# Sheet1.net
KiCad netlist of a schematic drawn in Altium Designer
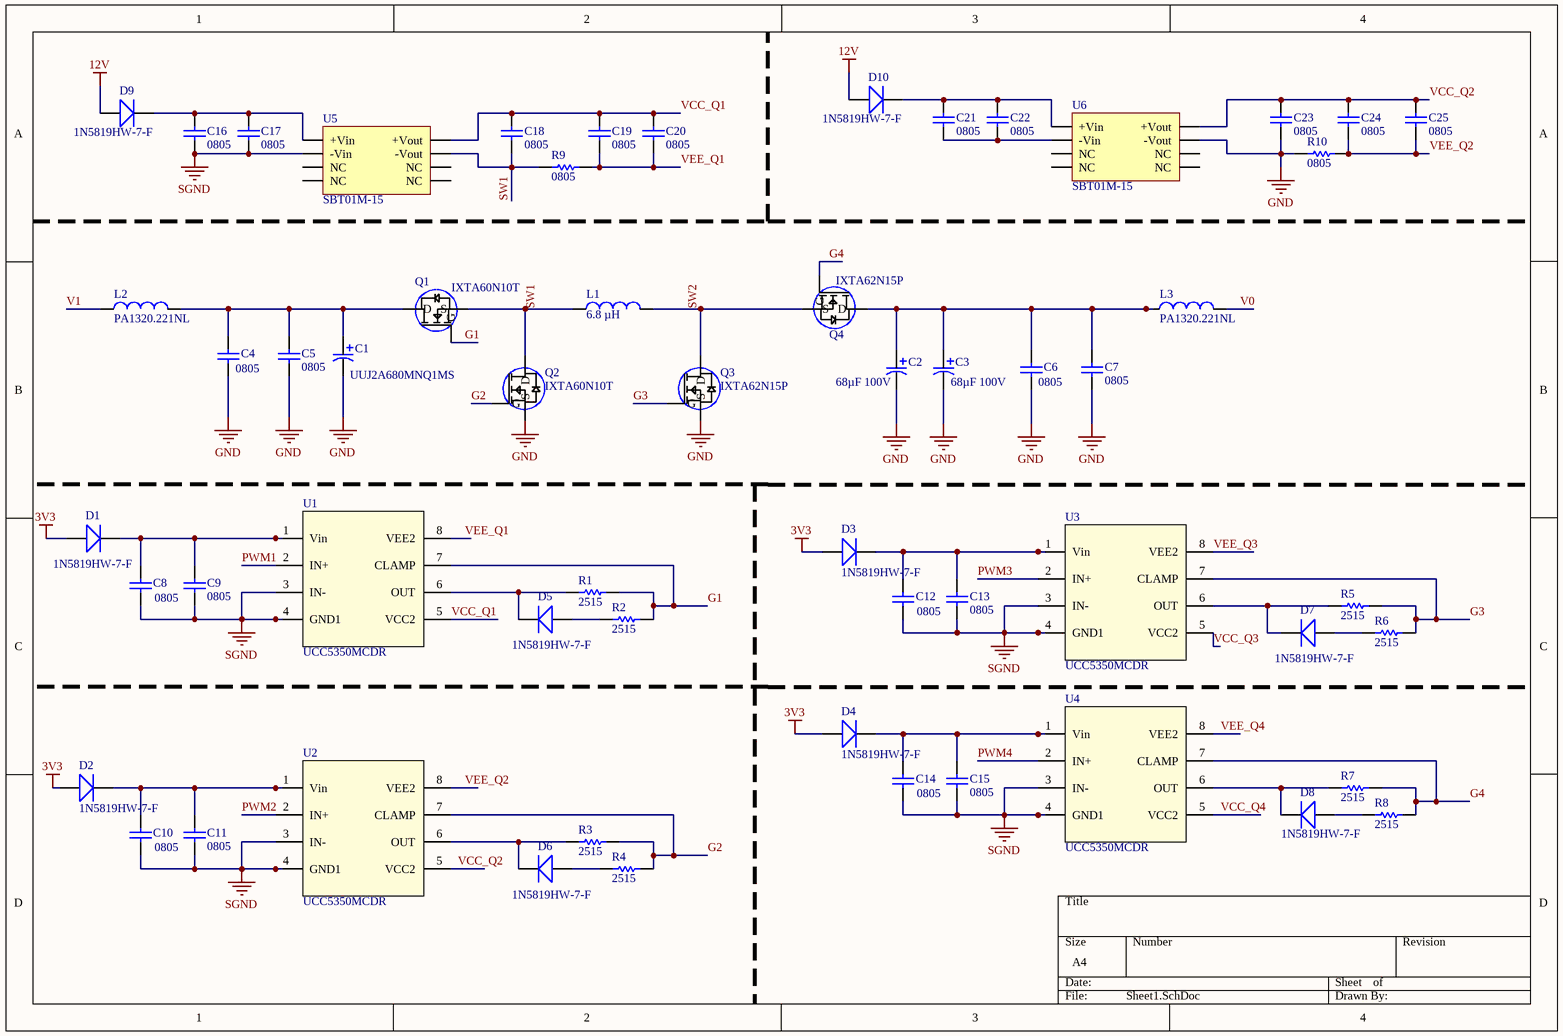
[diagram p0: Sheet1.SchDoc]

(export (version "E")
  (design (tool "Eeschema 10.0.6"))
  (components
    (comp (ref "C1")
      (value "UUJ2A680MNQ1MS")
      (footprint "UUJ2A680MNQ1MS")
      (description "68µF 100V Aluminum Electrolytic Capacitors")
      (libsource (lib "Schlib1") (part "UUJ2A680MNQ1MS"))
    )
    (comp (ref "C2")
      (value "68µF 100V")
      (footprint "UUJ2A680MNQ1MS")
      (description "68µF 100V Aluminum Electrolytic Capacitors")
      (libsource (lib "Schlib1") (part "UUJ2A680MNQ1MS"))
    )
    (comp (ref "C3")
      (value "68µF 100V")
      (footprint "UUJ2A680MNQ1MS")
      (description "68µF 100V Aluminum Electrolytic Capacitors")
      (libsource (lib "Schlib1") (part "UUJ2A680MNQ1MS"))
    )
    (comp (ref "C4")
      (value "0805")
      (footprint "0805 CAPACITOR")
      (description "1UF 100V CAP CER  X7S 0805")
      (libsource (lib "Schlib1") (part "0805CAP"))
    )
    (comp (ref "C5")
      (value "0805")
      (footprint "0805 CAPACITOR")
      (description "0.1UF 100V CAP CER X5R 0402")
      (libsource (lib "Schlib1") (part "0805CAP_1"))
    )
    (comp (ref "C6")
      (value "0805")
      (footprint "0805 CAPACITOR")
      (description "1UF 100V CAP CER  X7S 0805")
      (libsource (lib "Schlib1") (part "0805CAP"))
    )
    (comp (ref "C7")
      (value "0805")
      (footprint "0805 CAPACITOR")
      (description "0.1UF 100V CAP CER X5R 0402")
      (libsource (lib "Schlib1") (part "0805CAP_1"))
    )
    (comp (ref "C8")
      (value "0805")
      (footprint "0805 CAPACITOR")
      (description "4.7UF 100V CAP CER  X7S 0805")
      (libsource (lib "Schlib1") (part "0805 CAPACITANCE"))
    )
    (comp (ref "C9")
      (value "0805")
      (footprint "0805 CAPACITOR")
      (description "4.7UF 100V CAP CER  X7S 0805")
      (libsource (lib "Schlib1") (part "0805 CAPACITANCE"))
    )
    (comp (ref "C10")
      (value "0805")
      (footprint "0805 CAPACITOR")
      (description "4.7UF 100V CAP CER  X7S 0805")
      (libsource (lib "Schlib1") (part "0805 CAPACITANCE"))
    )
    (comp (ref "C11")
      (value "0805")
      (footprint "0805 CAPACITOR")
      (description "4.7UF 100V CAP CER  X7S 0805")
      (libsource (lib "Schlib1") (part "0805 CAPACITANCE"))
    )
    (comp (ref "C12")
      (value "0805")
      (footprint "0805 CAPACITOR")
      (description "4.7UF 100V CAP CER  X7S 0805")
      (libsource (lib "Schlib1") (part "0805 CAPACITANCE"))
    )
    (comp (ref "C13")
      (value "0805")
      (footprint "0805 CAPACITOR")
      (description "4.7UF 100V CAP CER  X7S 0805")
      (libsource (lib "Schlib1") (part "0805 CAPACITANCE"))
    )
    (comp (ref "C14")
      (value "0805")
      (footprint "0805 CAPACITOR")
      (description "4.7UF 100V CAP CER  X7S 0805")
      (libsource (lib "Schlib1") (part "0805 CAPACITANCE"))
    )
    (comp (ref "C15")
      (value "0805")
      (footprint "0805 CAPACITOR")
      (description "4.7UF 100V CAP CER  X7S 0805")
      (libsource (lib "Schlib1") (part "0805 CAPACITANCE"))
    )
    (comp (ref "C16")
      (value "0805")
      (footprint "0805 CAPACITOR")
      (description "4.7UF 100V CAP CER  X7S 0805")
      (libsource (lib "Schlib1") (part "0805 CAPACITANCE"))
    )
    (comp (ref "C17")
      (value "0805")
      (footprint "0805 CAPACITOR")
      (description "4.7UF 100V CAP CER  X7S 0805")
      (libsource (lib "Schlib1") (part "0805 CAPACITANCE"))
    )
    (comp (ref "C18")
      (value "0805")
      (footprint "0805 CAPACITOR")
      (description "4.7UF 100V CAP CER  X7S 0805")
      (libsource (lib "Schlib1") (part "0805 CAPACITANCE"))
    )
    (comp (ref "C19")
      (value "0805")
      (footprint "0805 CAPACITOR")
      (description "4.7UF 100V CAP CER  X7S 0805")
      (libsource (lib "Schlib1") (part "0805 CAPACITANCE"))
    )
    (comp (ref "C20")
      (value "0805")
      (footprint "0805 CAPACITOR")
      (description "4.7UF 100V CAP CER  X7S 0805")
      (libsource (lib "Schlib1") (part "0805 CAPACITANCE"))
    )
    (comp (ref "C21")
      (value "0805")
      (footprint "0805 CAPACITOR")
      (description "4.7UF 100V CAP CER  X7S 0805")
      (libsource (lib "Schlib1") (part "0805 CAPACITANCE"))
    )
    (comp (ref "C22")
      (value "0805")
      (footprint "0805 CAPACITOR")
      (description "4.7UF 100V CAP CER  X7S 0805")
      (libsource (lib "Schlib1") (part "0805 CAPACITANCE"))
    )
    (comp (ref "C23")
      (value "0805")
      (footprint "0805 CAPACITOR")
      (description "4.7UF 100V CAP CER  X7S 0805")
      (libsource (lib "Schlib1") (part "0805 CAPACITANCE"))
    )
    (comp (ref "C24")
      (value "0805")
      (footprint "0805 CAPACITOR")
      (description "4.7UF 100V CAP CER  X7S 0805")
      (libsource (lib "Schlib1") (part "0805 CAPACITANCE"))
    )
    (comp (ref "C25")
      (value "0805")
      (footprint "0805 CAPACITOR")
      (description "4.7UF 100V CAP CER  X7S 0805")
      (libsource (lib "Schlib1") (part "0805 CAPACITANCE"))
    )
    (comp (ref "D1")
      (value "1N5819HW-7-F")
      (footprint "1N5819HW-7-F_DIO-M")
      (description "40V 1A DIODE SCHOTTKY")
      (libsource (lib "Schlib1") (part "1N5819HW-7-F"))
    )
    (comp (ref "D2")
      (value "1N5819HW-7-F")
      (footprint "1N5819HW-7-F_DIO-M")
      (description "40V 1A DIODE SCHOTTKY")
      (libsource (lib "Schlib1") (part "1N5819HW-7-F"))
    )
    (comp (ref "D3")
      (value "1N5819HW-7-F")
      (footprint "1N5819HW-7-F_DIO-M")
      (description "40V 1A DIODE SCHOTTKY")
      (libsource (lib "Schlib1") (part "1N5819HW-7-F"))
    )
    (comp (ref "D4")
      (value "1N5819HW-7-F")
      (footprint "1N5819HW-7-F_DIO-M")
      (description "40V 1A DIODE SCHOTTKY")
      (libsource (lib "Schlib1") (part "1N5819HW-7-F"))
    )
    (comp (ref "D5")
      (value "1N5819HW-7-F")
      (footprint "1N5819HW-7-F_DIO-M")
      (description "40V 1A DIODE SCHOTTKY")
      (libsource (lib "Schlib1") (part "1N5819HW-7-F"))
    )
    (comp (ref "D6")
      (value "1N5819HW-7-F")
      (footprint "1N5819HW-7-F_DIO-M")
      (description "40V 1A DIODE SCHOTTKY")
      (libsource (lib "Schlib1") (part "1N5819HW-7-F"))
    )
    (comp (ref "D7")
      (value "1N5819HW-7-F")
      (footprint "1N5819HW-7-F_DIO-M")
      (description "40V 1A DIODE SCHOTTKY")
      (libsource (lib "Schlib1") (part "1N5819HW-7-F"))
    )
    (comp (ref "D8")
      (value "1N5819HW-7-F")
      (footprint "1N5819HW-7-F_DIO-M")
      (description "40V 1A DIODE SCHOTTKY")
      (libsource (lib "Schlib1") (part "1N5819HW-7-F"))
    )
    (comp (ref "D9")
      (value "1N5819HW-7-F")
      (footprint "1N5819HW-7-F_DIO-M")
      (description "40V 1A DIODE SCHOTTKY")
      (libsource (lib "Schlib1") (part "1N5819HW-7-F"))
    )
    (comp (ref "D10")
      (value "1N5819HW-7-F")
      (footprint "1N5819HW-7-F_DIO-M")
      (description "40V 1A DIODE SCHOTTKY")
      (libsource (lib "Schlib1") (part "1N5819HW-7-F"))
    )
    (comp (ref "L1")
      (value "6.8 µH")
      (footprint "MPX1D2213L6R8")
      (description "6.8UH 39A 3.3 MOHM SMD")
      (libsource (lib "Schlib1") (part "6.8 µH Shielded Wirewound Inductor"))
    )
    (comp (ref "L2")
      (value "PA1320.221NL")
      (footprint "PA1320.221NL")
      (libsource (lib "Schlib1") (part "PA1320.221NL"))
    )
    (comp (ref "L3")
      (value "PA1320.221NL")
      (footprint "PA1320.221NL")
      (libsource (lib "Schlib1") (part "PA1320.221NL"))
    )
    (comp (ref "Q1")
      (value "IXTA60N10T")
      (footprint "IXTA62N15P")
      (description "N-Channel 100 V 60A (Tc) 176W (Tc) Surface Mount TO-263AA")
      (libsource (lib "Schlib1") (part "IXTA60N10T"))
    )
    (comp (ref "Q2")
      (value "IXTA60N10T")
      (footprint "IXTA62N15P")
      (description "N-Channel 100 V 60A (Tc) 176W (Tc) Surface Mount TO-263AA")
      (libsource (lib "Schlib1") (part "IXTA60N10T"))
    )
    (comp (ref "Q3")
      (value "IXTA62N15P")
      (footprint "IXTA62N15P")
      (description "N-Channel 150 V 62A (Tc) 350W (Tc) Surface Mount TO-263AA")
      (libsource (lib "Schlib1") (part "IXTA62N15P"))
    )
    (comp (ref "Q4")
      (value "IXTA62N15P")
      (footprint "IXTA62N15P")
      (description "N-Channel 150 V 62A (Tc) 350W (Tc) Surface Mount TO-263AA")
      (libsource (lib "Schlib1") (part "IXTA62N15P"))
    )
    (comp (ref "R1")
      (value "2515")
      (footprint "2512 RESISTOR")
      (description "10 OHM RES SMD 10 OHM 5% 1W 2512")
      (libsource (lib "Schlib1") (part "2515 RESISTOR"))
    )
    (comp (ref "R2")
      (value "2515")
      (footprint "2512 RESISTOR")
      (description "10 OHM RES SMD 10 OHM 5% 1W 2512")
      (libsource (lib "Schlib1") (part "2515 RESISTOR"))
    )
    (comp (ref "R3")
      (value "2515")
      (footprint "2512 RESISTOR")
      (description "10 OHM RES SMD 10 OHM 5% 1W 2512")
      (libsource (lib "Schlib1") (part "2515 RESISTOR"))
    )
    (comp (ref "R4")
      (value "2515")
      (footprint "2512 RESISTOR")
      (description "10 OHM RES SMD 10 OHM 5% 1W 2512")
      (libsource (lib "Schlib1") (part "2515 RESISTOR"))
    )
    (comp (ref "R5")
      (value "2515")
      (footprint "2512 RESISTOR")
      (description "10 OHM RES SMD 10 OHM 5% 1W 2512")
      (libsource (lib "Schlib1") (part "2515 RESISTOR"))
    )
    (comp (ref "R6")
      (value "2515")
      (footprint "2512 RESISTOR")
      (description "10 OHM RES SMD 10 OHM 5% 1W 2512")
      (libsource (lib "Schlib1") (part "2515 RESISTOR"))
    )
    (comp (ref "R7")
      (value "2515")
      (footprint "2512 RESISTOR")
      (description "10 OHM RES SMD 10 OHM 5% 1W 2512")
      (libsource (lib "Schlib1") (part "2515 RESISTOR"))
    )
    (comp (ref "R8")
      (value "2515")
      (footprint "2512 RESISTOR")
      (description "10 OHM RES SMD 10 OHM 5% 1W 2512")
      (libsource (lib "Schlib1") (part "2515 RESISTOR"))
    )
    (comp (ref "R9")
      (value "0805")
      (footprint "0805 RESISTOR")
      (description "1K OHM 16V")
      (libsource (lib "Schlib1") (part "0805 RESISTOR"))
    )
    (comp (ref "R10")
      (value "0805")
      (footprint "0805 RESISTOR")
      (description "1K OHM 16V")
      (libsource (lib "Schlib1") (part "0805 RESISTOR"))
    )
    (comp (ref "U1")
      (value "UCC5350MCDR")
      (footprint "UCC5350MCDR")
      (description "No Description Available")
      (libsource (lib "Schlib1") (part "UCC5350MCDR"))
    )
    (comp (ref "U2")
      (value "UCC5350MCDR")
      (footprint "UCC5350MCDR")
      (description "No Description Available")
      (libsource (lib "Schlib1") (part "UCC5350MCDR"))
    )
    (comp (ref "U3")
      (value "UCC5350MCDR")
      (footprint "UCC5350MCDR")
      (description "No Description Available")
      (libsource (lib "Schlib1") (part "UCC5350MCDR"))
    )
    (comp (ref "U4")
      (value "UCC5350MCDR")
      (footprint "UCC5350MCDR")
      (description "No Description Available")
      (libsource (lib "Schlib1") (part "UCC5350MCDR"))
    )
    (comp (ref "U5")
      (value "SBT01M-15")
      (footprint "SBT01M-15")
      (libsource (lib "Schlib1") (part "SBT01M-15"))
    )
    (comp (ref "U6")
      (value "SBT01M-15")
      (footprint "SBT01M-15")
      (libsource (lib "Schlib1") (part "SBT01M-15"))
    )
  )
  (nets
    (net (code "1") (name "/G1") (class "Default")
      (node (ref "Q1") (pin "1") (pinfunction "G_1") (pintype "passive"))
      (node (ref "R1") (pin "2") (pinfunction "2_2") (pintype "passive"))
      (node (ref "R2") (pin "2") (pinfunction "2_2") (pintype "passive"))
      (node (ref "U1") (pin "7") (pinfunction "CLAMP_7") (pintype "passive"))
    )
    (net (code "2") (name "/G2") (class "Default")
      (node (ref "Q2") (pin "1") (pinfunction "G_1") (pintype "passive"))
      (node (ref "R3") (pin "2") (pinfunction "2_2") (pintype "passive"))
      (node (ref "R4") (pin "2") (pinfunction "2_2") (pintype "passive"))
      (node (ref "U2") (pin "7") (pinfunction "CLAMP_7") (pintype "passive"))
    )
    (net (code "3") (name "/G3") (class "Default")
      (node (ref "Q3") (pin "1") (pinfunction "G_1") (pintype "passive"))
      (node (ref "R5") (pin "2") (pinfunction "2_2") (pintype "passive"))
      (node (ref "R6") (pin "2") (pinfunction "2_2") (pintype "passive"))
      (node (ref "U3") (pin "7") (pinfunction "CLAMP_7") (pintype "passive"))
    )
    (net (code "4") (name "/G4") (class "Default")
      (node (ref "Q4") (pin "1") (pinfunction "G_1") (pintype "passive"))
      (node (ref "R7") (pin "2") (pinfunction "2_2") (pintype "passive"))
      (node (ref "R8") (pin "2") (pinfunction "2_2") (pintype "passive"))
      (node (ref "U4") (pin "7") (pinfunction "CLAMP_7") (pintype "passive"))
    )
    (net (code "5") (name "/PWM1") (class "Default")
      (node (ref "U1") (pin "2") (pinfunction "IN+_2") (pintype "passive"))
    )
    (net (code "6") (name "/PWM2") (class "Default")
      (node (ref "U2") (pin "2") (pinfunction "IN+_2") (pintype "passive"))
    )
    (net (code "7") (name "/PWM3") (class "Default")
      (node (ref "U3") (pin "2") (pinfunction "IN+_2") (pintype "passive"))
    )
    (net (code "8") (name "/PWM4") (class "Default")
      (node (ref "U4") (pin "2") (pinfunction "IN+_2") (pintype "passive"))
    )
    (net (code "9") (name "/SW1") (class "Default")
      (node (ref "C18") (pin "1") (pinfunction "1_1") (pintype "passive"))
      (node (ref "L1") (pin "1") (pinfunction "1_1") (pintype "passive"))
      (node (ref "Q1") (pin "3") (pinfunction "S_3") (pintype "passive"))
      (node (ref "Q2") (pin "2") (pinfunction "D_2") (pintype "passive"))
      (node (ref "R9") (pin "1") (pinfunction "1_1") (pintype "passive"))
      (node (ref "U5") (pin "4") (pinfunction "-Vout_4") (pintype "passive"))
    )
    (net (code "10") (name "/SW2") (class "Default")
      (node (ref "L1") (pin "2") (pinfunction "2_2") (pintype "passive"))
      (node (ref "Q3") (pin "2") (pinfunction "D_2") (pintype "passive"))
      (node (ref "Q4") (pin "3") (pinfunction "S_3") (pintype "passive"))
    )
    (net (code "11") (name "/V0") (class "Default")
      (node (ref "L3") (pin "2") (pinfunction "2_2") (pintype "passive"))
    )
    (net (code "12") (name "/V1") (class "Default")
      (node (ref "L2") (pin "1") (pinfunction "1_1") (pintype "passive"))
    )
    (net (code "13") (name "/VCC_Q1") (class "Default")
      (node (ref "C18") (pin "2") (pinfunction "2_2") (pintype "passive"))
      (node (ref "C19") (pin "2") (pinfunction "2_2") (pintype "passive"))
      (node (ref "C20") (pin "2") (pinfunction "2_2") (pintype "passive"))
      (node (ref "U1") (pin "5") (pinfunction "VCC2_5") (pintype "passive"))
      (node (ref "U5") (pin "5") (pinfunction "+Vout_5") (pintype "passive"))
    )
    (net (code "14") (name "/VCC_Q2") (class "Default")
      (node (ref "C23") (pin "2") (pinfunction "2_2") (pintype "passive"))
      (node (ref "C24") (pin "2") (pinfunction "2_2") (pintype "passive"))
      (node (ref "C25") (pin "2") (pinfunction "2_2") (pintype "passive"))
      (node (ref "U2") (pin "5") (pinfunction "VCC2_5") (pintype "passive"))
      (node (ref "U6") (pin "5") (pinfunction "+Vout_5") (pintype "passive"))
    )
    (net (code "15") (name "/VCC_Q3") (class "Default")
      (node (ref "U3") (pin "5") (pinfunction "VCC2_5") (pintype "passive"))
    )
    (net (code "16") (name "/VCC_Q4") (class "Default")
      (node (ref "U4") (pin "5") (pinfunction "VCC2_5") (pintype "passive"))
    )
    (net (code "17") (name "/VEE_Q1") (class "Default")
      (node (ref "C19") (pin "1") (pinfunction "1_1") (pintype "passive"))
      (node (ref "C20") (pin "1") (pinfunction "1_1") (pintype "passive"))
      (node (ref "R9") (pin "2") (pinfunction "2_2") (pintype "passive"))
      (node (ref "U1") (pin "8") (pinfunction "VEE2_8") (pintype "passive"))
    )
    (net (code "18") (name "/VEE_Q2") (class "Default")
      (node (ref "C24") (pin "1") (pinfunction "1_1") (pintype "passive"))
      (node (ref "C25") (pin "1") (pinfunction "1_1") (pintype "passive"))
      (node (ref "R10") (pin "2") (pinfunction "2_2") (pintype "passive"))
      (node (ref "U2") (pin "8") (pinfunction "VEE2_8") (pintype "passive"))
    )
    (net (code "19") (name "/VEE_Q3") (class "Default")
      (node (ref "U3") (pin "8") (pinfunction "VEE2_8") (pintype "passive"))
    )
    (net (code "20") (name "/VEE_Q4") (class "Default")
      (node (ref "U4") (pin "8") (pinfunction "VEE2_8") (pintype "passive"))
    )
    (net (code "21") (name "3V3") (class "Default")
      (node (ref "D1") (pin "1") (pinfunction "1_1") (pintype "passive"))
      (node (ref "D2") (pin "1") (pinfunction "1_1") (pintype "passive"))
      (node (ref "D3") (pin "1") (pinfunction "1_1") (pintype "passive"))
      (node (ref "D4") (pin "1") (pinfunction "1_1") (pintype "passive"))
    )
    (net (code "22") (name "12V") (class "Default")
      (node (ref "D10") (pin "1") (pinfunction "1_1") (pintype "passive"))
      (node (ref "D9") (pin "1") (pinfunction "1_1") (pintype "passive"))
    )
    (net (code "23") (name "GND") (class "Default")
      (node (ref "C1") (pin "2") (pinfunction "2_2") (pintype "passive"))
      (node (ref "C2") (pin "2") (pinfunction "2_2") (pintype "passive"))
      (node (ref "C23") (pin "1") (pinfunction "1_1") (pintype "passive"))
      (node (ref "C3") (pin "2") (pinfunction "2_2") (pintype "passive"))
      (node (ref "C4") (pin "2") (pinfunction "2_2") (pintype "passive"))
      (node (ref "C5") (pin "1") (pinfunction "1_1") (pintype "passive"))
      (node (ref "C6") (pin "2") (pinfunction "2_2") (pintype "passive"))
      (node (ref "C7") (pin "1") (pinfunction "1_1") (pintype "passive"))
      (node (ref "Q2") (pin "3") (pinfunction "S_3") (pintype "passive"))
      (node (ref "Q3") (pin "3") (pinfunction "S_3") (pintype "passive"))
      (node (ref "R10") (pin "1") (pinfunction "1_1") (pintype "passive"))
      (node (ref "U6") (pin "4") (pinfunction "-Vout_4") (pintype "passive"))
    )
    (net (code "24") (name "Net-(D5-Pad1)") (class "Default")
      (node (ref "D5") (pin "1") (pinfunction "1_1") (pintype "passive"))
      (node (ref "R2") (pin "1") (pinfunction "1_1") (pintype "passive"))
    )
    (net (code "25") (name "Net-(D6-Pad1)") (class "Default")
      (node (ref "D6") (pin "1") (pinfunction "1_1") (pintype "passive"))
      (node (ref "R4") (pin "1") (pinfunction "1_1") (pintype "passive"))
    )
    (net (code "26") (name "Net-(D7-Pad1)") (class "Default")
      (node (ref "D7") (pin "1") (pinfunction "1_1") (pintype "passive"))
      (node (ref "R6") (pin "1") (pinfunction "1_1") (pintype "passive"))
    )
    (net (code "27") (name "Net-(D8-Pad1)") (class "Default")
      (node (ref "D8") (pin "1") (pinfunction "1_1") (pintype "passive"))
      (node (ref "R8") (pin "1") (pinfunction "1_1") (pintype "passive"))
    )
    (net (code "28") (name "Net-(Q1-D)") (class "Default")
      (node (ref "C1") (pin "1") (pinfunction "1_1") (pintype "passive"))
      (node (ref "C4") (pin "1") (pinfunction "1_1") (pintype "passive"))
      (node (ref "C5") (pin "2") (pinfunction "2_2") (pintype "passive"))
      (node (ref "L2") (pin "2") (pinfunction "2_2") (pintype "passive"))
      (node (ref "Q1") (pin "2") (pinfunction "D_2") (pintype "passive"))
    )
    (net (code "29") (name "Net-(Q4-D)") (class "Default")
      (node (ref "C2") (pin "1") (pinfunction "1_1") (pintype "passive"))
      (node (ref "C3") (pin "1") (pinfunction "1_1") (pintype "passive"))
      (node (ref "C6") (pin "1") (pinfunction "1_1") (pintype "passive"))
      (node (ref "C7") (pin "2") (pinfunction "2_2") (pintype "passive"))
      (node (ref "L3") (pin "1") (pinfunction "1_1") (pintype "passive"))
      (node (ref "Q4") (pin "2") (pinfunction "D_2") (pintype "passive"))
    )
    (net (code "30") (name "Net-(U1-OUT)") (class "Default")
      (node (ref "D5") (pin "2") (pinfunction "2_2") (pintype "passive"))
      (node (ref "R1") (pin "1") (pinfunction "1_1") (pintype "passive"))
      (node (ref "U1") (pin "6") (pinfunction "OUT_6") (pintype "passive"))
    )
    (net (code "31") (name "Net-(U1-Vin)") (class "Default")
      (node (ref "C8") (pin "2") (pinfunction "2_2") (pintype "passive"))
      (node (ref "C9") (pin "2") (pinfunction "2_2") (pintype "passive"))
      (node (ref "D1") (pin "2") (pinfunction "2_2") (pintype "passive"))
      (node (ref "U1") (pin "1") (pinfunction "Vin_1") (pintype "passive"))
    )
    (net (code "32") (name "Net-(U2-OUT)") (class "Default")
      (node (ref "D6") (pin "2") (pinfunction "2_2") (pintype "passive"))
      (node (ref "R3") (pin "1") (pinfunction "1_1") (pintype "passive"))
      (node (ref "U2") (pin "6") (pinfunction "OUT_6") (pintype "passive"))
    )
    (net (code "33") (name "Net-(U2-Vin)") (class "Default")
      (node (ref "C10") (pin "2") (pinfunction "2_2") (pintype "passive"))
      (node (ref "C11") (pin "2") (pinfunction "2_2") (pintype "passive"))
      (node (ref "D2") (pin "2") (pinfunction "2_2") (pintype "passive"))
      (node (ref "U2") (pin "1") (pinfunction "Vin_1") (pintype "passive"))
    )
    (net (code "34") (name "Net-(U3-OUT)") (class "Default")
      (node (ref "D7") (pin "2") (pinfunction "2_2") (pintype "passive"))
      (node (ref "R5") (pin "1") (pinfunction "1_1") (pintype "passive"))
      (node (ref "U3") (pin "6") (pinfunction "OUT_6") (pintype "passive"))
    )
    (net (code "35") (name "Net-(U3-Vin)") (class "Default")
      (node (ref "C12") (pin "2") (pinfunction "2_2") (pintype "passive"))
      (node (ref "C13") (pin "2") (pinfunction "2_2") (pintype "passive"))
      (node (ref "D3") (pin "2") (pinfunction "2_2") (pintype "passive"))
      (node (ref "U3") (pin "1") (pinfunction "Vin_1") (pintype "passive"))
    )
    (net (code "36") (name "Net-(U4-OUT)") (class "Default")
      (node (ref "D8") (pin "2") (pinfunction "2_2") (pintype "passive"))
      (node (ref "R7") (pin "1") (pinfunction "1_1") (pintype "passive"))
      (node (ref "U4") (pin "6") (pinfunction "OUT_6") (pintype "passive"))
    )
    (net (code "37") (name "Net-(U4-Vin)") (class "Default")
      (node (ref "C14") (pin "2") (pinfunction "2_2") (pintype "passive"))
      (node (ref "C15") (pin "2") (pinfunction "2_2") (pintype "passive"))
      (node (ref "D4") (pin "2") (pinfunction "2_2") (pintype "passive"))
      (node (ref "U4") (pin "1") (pinfunction "Vin_1") (pintype "passive"))
    )
    (net (code "38") (name "Net-(U5-+Vin)") (class "Default")
      (node (ref "C16") (pin "1") (pinfunction "1_1") (pintype "passive"))
      (node (ref "C17") (pin "2") (pinfunction "2_2") (pintype "passive"))
      (node (ref "D9") (pin "2") (pinfunction "2_2") (pintype "passive"))
      (node (ref "U5") (pin "2") (pinfunction "+Vin_2") (pintype "passive"))
    )
    (net (code "39") (name "Net-(U6-+Vin)") (class "Default")
      (node (ref "C21") (pin "1") (pinfunction "1_1") (pintype "passive"))
      (node (ref "C22") (pin "2") (pinfunction "2_2") (pintype "passive"))
      (node (ref "D10") (pin "2") (pinfunction "2_2") (pintype "passive"))
      (node (ref "U6") (pin "2") (pinfunction "+Vin_2") (pintype "passive"))
    )
    (net (code "40") (name "Net-(U6--Vin)") (class "Default")
      (node (ref "C21") (pin "2") (pinfunction "2_2") (pintype "passive"))
      (node (ref "C22") (pin "1") (pinfunction "1_1") (pintype "passive"))
      (node (ref "U6") (pin "1") (pinfunction "-Vin_1") (pintype "passive"))
    )
    (net (code "41") (name "SGND") (class "Default")
      (node (ref "C10") (pin "1") (pinfunction "1_1") (pintype "passive"))
      (node (ref "C11") (pin "1") (pinfunction "1_1") (pintype "passive"))
      (node (ref "C12") (pin "1") (pinfunction "1_1") (pintype "passive"))
      (node (ref "C13") (pin "1") (pinfunction "1_1") (pintype "passive"))
      (node (ref "C14") (pin "1") (pinfunction "1_1") (pintype "passive"))
      (node (ref "C15") (pin "1") (pinfunction "1_1") (pintype "passive"))
      (node (ref "C16") (pin "2") (pinfunction "2_2") (pintype "passive"))
      (node (ref "C17") (pin "1") (pinfunction "1_1") (pintype "passive"))
      (node (ref "C8") (pin "1") (pinfunction "1_1") (pintype "passive"))
      (node (ref "C9") (pin "1") (pinfunction "1_1") (pintype "passive"))
      (node (ref "U1") (pin "3") (pinfunction "IN-_3") (pintype "passive"))
      (node (ref "U1") (pin "4") (pinfunction "GND1_4") (pintype "passive"))
      (node (ref "U2") (pin "3") (pinfunction "IN-_3") (pintype "passive"))
      (node (ref "U2") (pin "4") (pinfunction "GND1_4") (pintype "passive"))
      (node (ref "U3") (pin "3") (pinfunction "IN-_3") (pintype "passive"))
      (node (ref "U3") (pin "4") (pinfunction "GND1_4") (pintype "passive"))
      (node (ref "U4") (pin "3") (pinfunction "IN-_3") (pintype "passive"))
      (node (ref "U4") (pin "4") (pinfunction "GND1_4") (pintype "passive"))
      (node (ref "U5") (pin "1") (pinfunction "-Vin_1") (pintype "passive"))
    )
    (net (code "42") (name "unconnected-(U5-NC-Pad3)") (class "Default")
      (node (ref "U5") (pin "3") (pinfunction "NC_3") (pintype "passive"))
    )
    (net (code "43") (name "unconnected-(U5-NC-Pad6)") (class "Default")
      (node (ref "U5") (pin "6") (pinfunction "NC_6") (pintype "passive"))
    )
    (net (code "44") (name "unconnected-(U5-NC-Pad7)") (class "Default")
      (node (ref "U5") (pin "7") (pinfunction "NC_7") (pintype "passive"))
    )
    (net (code "45") (name "unconnected-(U5-NC-Pad8)") (class "Default")
      (node (ref "U5") (pin "8") (pinfunction "NC_8") (pintype "passive"))
    )
    (net (code "46") (name "unconnected-(U6-NC-Pad3)") (class "Default")
      (node (ref "U6") (pin "3") (pinfunction "NC_3") (pintype "passive"))
    )
    (net (code "47") (name "unconnected-(U6-NC-Pad6)") (class "Default")
      (node (ref "U6") (pin "6") (pinfunction "NC_6") (pintype "passive"))
    )
    (net (code "48") (name "unconnected-(U6-NC-Pad7)") (class "Default")
      (node (ref "U6") (pin "7") (pinfunction "NC_7") (pintype "passive"))
    )
    (net (code "49") (name "unconnected-(U6-NC-Pad8)") (class "Default")
      (node (ref "U6") (pin "8") (pinfunction "NC_8") (pintype "passive"))
    )
  )
)
